# 6_Accumulator_Indicator.net
KiCad netlist of a schematic drawn in Altium Designer
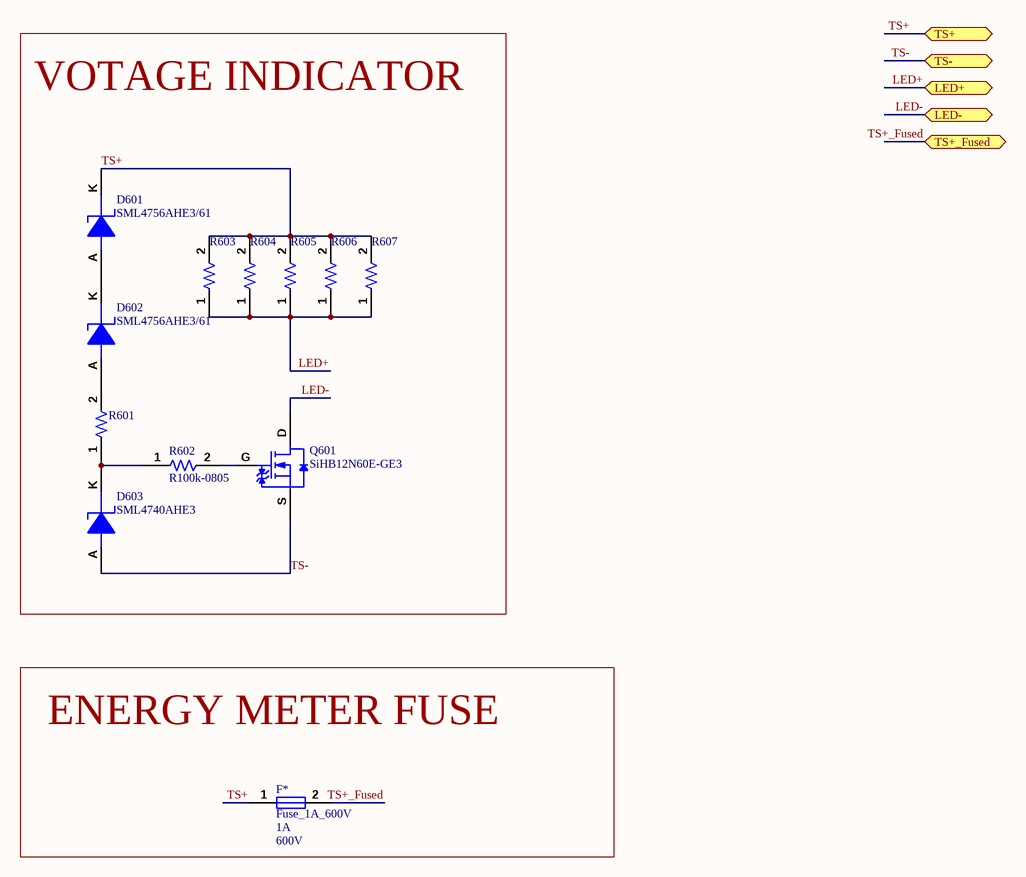
[diagram p0: [6]Accumulator_Indicator.SchDoc]

(export (version "E")
  (design (tool "Eeschema 10.0.6"))
  (components
    (comp (ref "D601")
      (value "SML4756AHE3/61")
      (footprint "DIOM4227X23N")
      (description "Zener Diode, 47V V(Z), 5%, 1W, Silicon, Unidirectional, DO-214AC")
      (libsource (lib "EMEA- E-Tech Racing- I'Escola d'Enginyeria de Barcelona Est") (part "DZ-0.01/75-SOD-123"))
    )
    (comp (ref "D602")
      (value "SML4756AHE3/61")
      (footprint "DIOM4227X23N")
      (description "Zener Diode, 47V V(Z), 5%, 1W, Silicon, Unidirectional, DO-214AC")
      (libsource (lib "EMEA- E-Tech Racing- I'Escola d'Enginyeria de Barcelona Est") (part "DZ-0.01/75-SOD-123"))
    )
    (comp (ref "D603")
      (value "SML4740AHE3")
      (footprint "DIOM4227X23N")
      (description "Zener Diode, 10V V(Z), 5%, 1W, Silicon, Unidirectional, DO-214AC")
      (libsource (lib "EMEA- E-Tech Racing- I'Escola d'Enginyeria de Barcelona Est") (part "DZ-0.01/75-SOD-123"))
    )
    (comp (ref "F*")
      (value "Fuse_1A_600V")
      (footprint "Fuse_485001")
      (description "Surface Mount Fuses 600V 1A Fast Acting")
      (fields
        (field (name "CURRENT RATING") "1A")
        (field (name "VOLTAGE RATING (DC)") "600V")
        (field (name ".CREATOR") "DO")
      )
      (libsource (lib "EMEA- E-Tech Racing- I'Escola d'Enginyeria de Barcelona Est") (part "Fuse_1A_63V_1206"))
    )
    (comp (ref "Q601")
      (value "SiHB12N60E-GE3")
      (footprint "SiHB12N60E-GE3-Footprint-1")
      (libsource (lib "EMEA- E-Tech Racing- I'Escola d'Enginyeria de Barcelona Est") (part "TRT-NCH-3/35-CPH"))
    )
    (comp (ref "R601")
      (value "PR03000201003JAC00")
      (footprint "PR03000202203JDC00-Footprint-1")
      (description "Fixed Resistor, Metal Film, 3W, 100000ohm, 750V, 5% +/-Tol, 250ppm/Cel, Through Hole Mount")
      (fields (field (name "TOLERANCE") "5%") (field (name "POWER") "3W"))
      (libsource (lib "EMEA- E-Tech Racing- I'Escola d'Enginyeria de Barcelona Est") (part "R9.09K-1206FTK"))
    )
    (comp (ref "R602")
      (value "R100k-0805")
      (footprint "RESC2013X70X40NL20T20")
      (fields (field (name "POWER") "125mW") (field (name "TOLERANCE") "5%"))
      (libsource (lib "EMEA- E-Tech Racing- I'Escola d'Enginyeria de Barcelona Est") (part "R9.09K-1206FTK"))
    )
    (comp (ref "R603")
      (value "PR03000202203JDC00")
      (footprint "PR03000202203JDC00-Footprint-1")
      (description "Fixed Resistor, Metal Film, 3W, 220000ohm, 750V, 5% +/-Tol, 250ppm/Cel, Through Hole Mount")
      (libsource (lib "EMEA- E-Tech Racing- I'Escola d'Enginyeria de Barcelona Est") (part "R9.09K-1206FTK"))
    )
    (comp (ref "R604")
      (value "PR03000202203JDC00")
      (footprint "PR03000202203JDC00-Footprint-1")
      (description "Fixed Resistor, Metal Film, 3W, 220000ohm, 750V, 5% +/-Tol, 250ppm/Cel, Through Hole Mount")
      (libsource (lib "EMEA- E-Tech Racing- I'Escola d'Enginyeria de Barcelona Est") (part "R9.09K-1206FTK"))
    )
    (comp (ref "R605")
      (value "PR03000202203JDC00")
      (footprint "PR03000202203JDC00-Footprint-1")
      (description "Fixed Resistor, Metal Film, 3W, 220000ohm, 750V, 5% +/-Tol, 250ppm/Cel, Through Hole Mount")
      (libsource (lib "EMEA- E-Tech Racing- I'Escola d'Enginyeria de Barcelona Est") (part "R9.09K-1206FTK"))
    )
    (comp (ref "R606")
      (value "PR03000202203JDC00")
      (footprint "PR03000202203JDC00-Footprint-1")
      (description "Fixed Resistor, Metal Film, 3W, 220000ohm, 750V, 5% +/-Tol, 250ppm/Cel, Through Hole Mount")
      (libsource (lib "EMEA- E-Tech Racing- I'Escola d'Enginyeria de Barcelona Est") (part "R9.09K-1206FTK"))
    )
    (comp (ref "R607")
      (value "PR03000202203JDC00")
      (footprint "PR03000202203JDC00-Footprint-1")
      (description "Fixed Resistor, Metal Film, 3W, 220000ohm, 750V, 5% +/-Tol, 250ppm/Cel, Through Hole Mount")
      (libsource (lib "EMEA- E-Tech Racing- I'Escola d'Enginyeria de Barcelona Est") (part "R9.09K-1206FTK"))
    )
  )
  (nets
    (net (code "1") (name "/LED+") (class "Default")
      (node (ref "R603") (pin "1") (pinfunction "1_1") (pintype "passive"))
      (node (ref "R604") (pin "1") (pinfunction "1_1") (pintype "passive"))
      (node (ref "R605") (pin "1") (pinfunction "1_1") (pintype "passive"))
      (node (ref "R606") (pin "1") (pinfunction "1_1") (pintype "passive"))
      (node (ref "R607") (pin "1") (pinfunction "1_1") (pintype "passive"))
    )
    (net (code "2") (name "/LED-") (class "Default")
      (node (ref "Q601") (pin "D") (pinfunction "D_D") (pintype "passive"))
    )
    (net (code "3") (name "/TS+") (class "Default")
      (node (ref "D601") (pin "K") (pinfunction "K_K") (pintype "passive"))
      (node (ref "F*") (pin "1") (pinfunction "1_1") (pintype "passive"))
      (node (ref "R603") (pin "2") (pinfunction "2_2") (pintype "passive"))
      (node (ref "R604") (pin "2") (pinfunction "2_2") (pintype "passive"))
      (node (ref "R605") (pin "2") (pinfunction "2_2") (pintype "passive"))
      (node (ref "R606") (pin "2") (pinfunction "2_2") (pintype "passive"))
      (node (ref "R607") (pin "2") (pinfunction "2_2") (pintype "passive"))
    )
    (net (code "4") (name "/TS+_Fused") (class "Default")
      (node (ref "F*") (pin "2") (pinfunction "2_2") (pintype "passive"))
    )
    (net (code "5") (name "/TS-") (class "Default")
      (node (ref "D603") (pin "A") (pinfunction "A_A") (pintype "passive"))
      (node (ref "Q601") (pin "S") (pinfunction "S_S") (pintype "passive"))
    )
    (net (code "6") (name "Net-(D601-PadA)") (class "Default")
      (node (ref "D601") (pin "A") (pinfunction "A_A") (pintype "passive"))
      (node (ref "D602") (pin "K") (pinfunction "K_K") (pintype "passive"))
    )
    (net (code "7") (name "Net-(D602-PadA)") (class "Default")
      (node (ref "D602") (pin "A") (pinfunction "A_A") (pintype "passive"))
      (node (ref "R601") (pin "2") (pinfunction "2_2") (pintype "passive"))
    )
    (net (code "8") (name "Net-(D603-PadK)") (class "Default")
      (node (ref "D603") (pin "K") (pinfunction "K_K") (pintype "passive"))
      (node (ref "R601") (pin "1") (pinfunction "1_1") (pintype "passive"))
      (node (ref "R602") (pin "1") (pinfunction "1_1") (pintype "passive"))
    )
    (net (code "9") (name "Net-(Q601-PadG)") (class "Default")
      (node (ref "Q601") (pin "G") (pinfunction "G_G") (pintype "passive"))
      (node (ref "R602") (pin "2") (pinfunction "2_2") (pintype "passive"))
    )
  )
)
